# mainboard.net
KiCad netlist of a schematic drawn in EAGLE
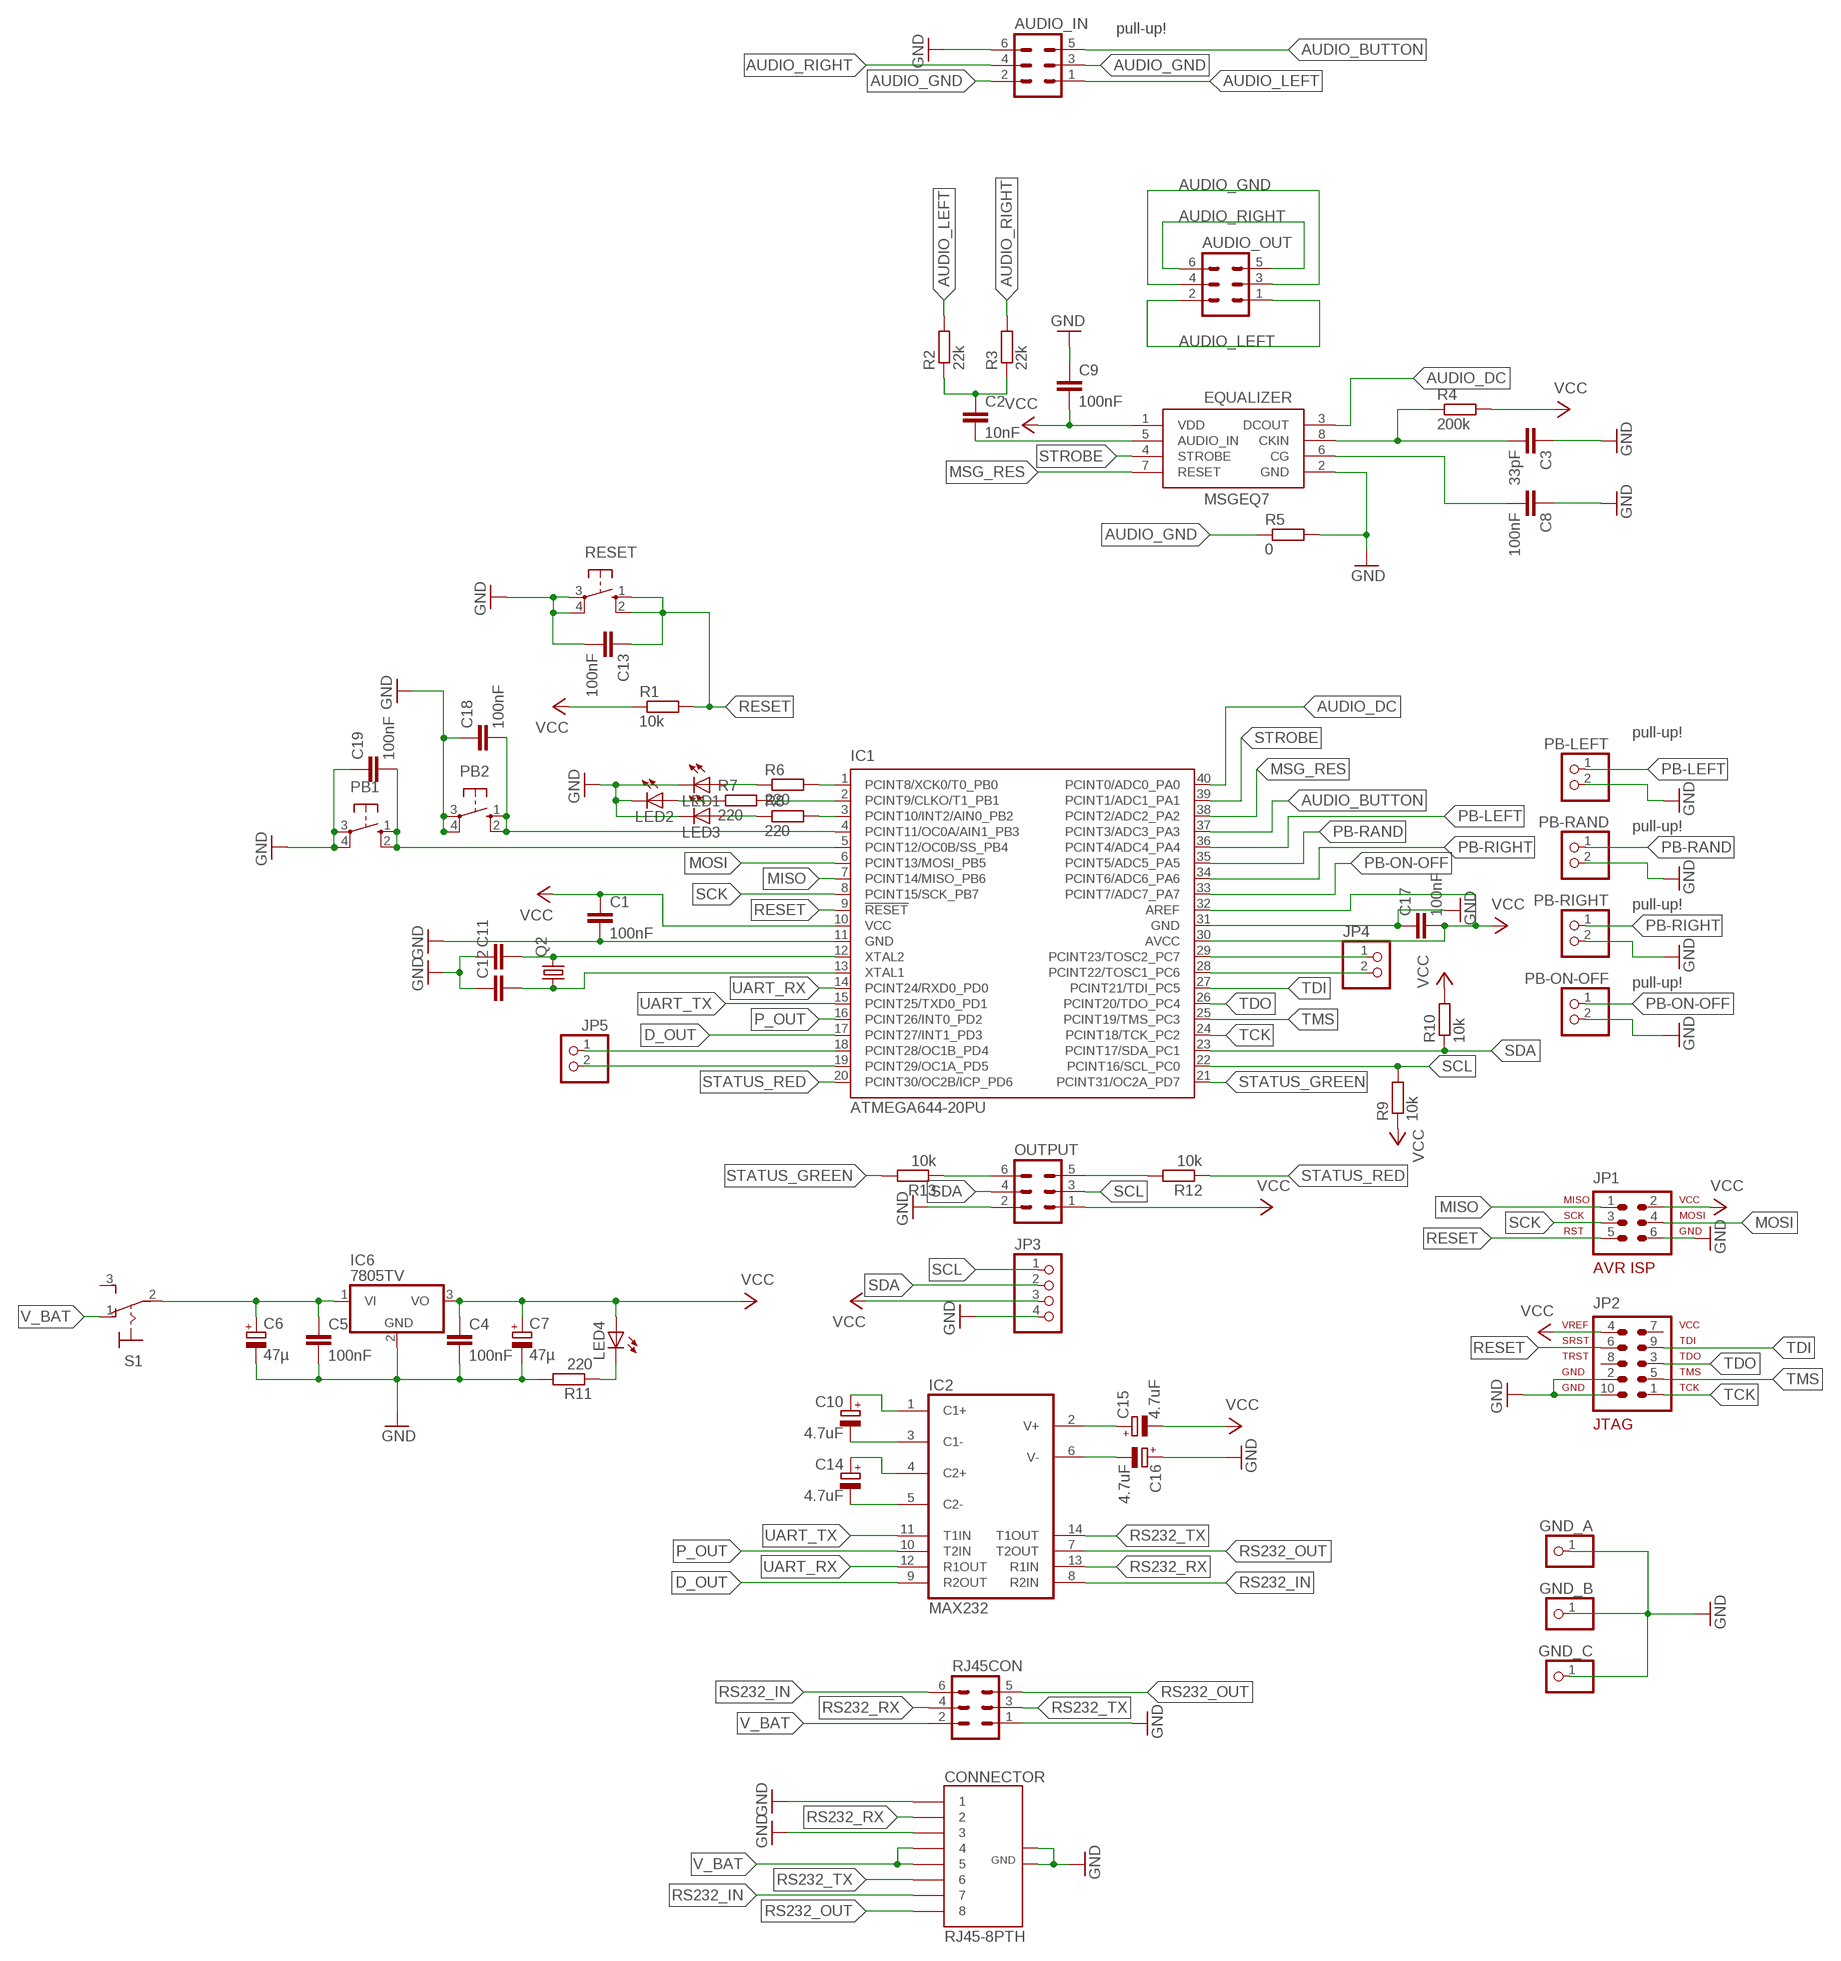
[diagram p0: schematic, sheet 1]

(export (version "E")
  (design (tool "Eeschema 10.0.6"))
  (components
    (comp (ref "AUDIO_IN")
      (value "ML6")
      (footprint "eagle-import:ML6")
      (fields (field (name "OC_FARNELL") "unknown") (field (name "OC_NEWARK") "unknown"))
      (libsource (lib "eagle-import") (part "ML6"))
    )
    (comp (ref "AUDIO_OUT")
      (value "ML6")
      (footprint "eagle-import:ML6")
      (libsource (lib "eagle-import") (part "ML6"))
    )
    (comp (ref "C1")
      (value "100nF")
      (footprint "eagle-import:C1206")
      (libsource (lib "eagle-import") (part "C-EUC1206"))
    )
    (comp (ref "C2")
      (value "10nF")
      (footprint "eagle-import:C1206")
      (libsource (lib "eagle-import") (part "C-EUC1206"))
    )
    (comp (ref "C3")
      (value "33pF")
      (footprint "eagle-import:C1206")
      (libsource (lib "eagle-import") (part "C-EUC1206"))
    )
    (comp (ref "C4")
      (value "100nF")
      (footprint "eagle-import:C1206")
      (libsource (lib "eagle-import") (part "C-EUC1206"))
    )
    (comp (ref "C5")
      (value "100nF")
      (footprint "eagle-import:C1206")
      (libsource (lib "eagle-import") (part "C-EUC1206"))
    )
    (comp (ref "C6")
      (value "47µ")
      (footprint "eagle-import:E2,5-6")
      (libsource (lib "eagle-import") (part "CPOL-EUE2.5-6"))
    )
    (comp (ref "C7")
      (value "47µ")
      (footprint "eagle-import:E2,5-6")
      (libsource (lib "eagle-import") (part "CPOL-EUE2.5-6"))
    )
    (comp (ref "C8")
      (value "100nF")
      (footprint "eagle-import:C1206")
      (libsource (lib "eagle-import") (part "C-EUC1206"))
    )
    (comp (ref "C9")
      (value "100nF")
      (footprint "eagle-import:C1206")
      (libsource (lib "eagle-import") (part "C-EUC1206"))
    )
    (comp (ref "C10")
      (value "4.7uF")
      (footprint "eagle-import:E2-5")
      (libsource (lib "eagle-import") (part "CPOL-EUE2-5"))
    )
    (comp (ref "C11")
      (value "C-EUC1206")
      (footprint "eagle-import:C1206")
      (libsource (lib "eagle-import") (part "C-EUC1206"))
    )
    (comp (ref "C12")
      (value "C-EUC1206")
      (footprint "eagle-import:C1206")
      (libsource (lib "eagle-import") (part "C-EUC1206"))
    )
    (comp (ref "C13")
      (value "100nF")
      (footprint "eagle-import:C1206")
      (libsource (lib "eagle-import") (part "C-EUC1206"))
    )
    (comp (ref "C14")
      (value "4.7uF")
      (footprint "eagle-import:E2-5")
      (libsource (lib "eagle-import") (part "CPOL-EUE2-5"))
    )
    (comp (ref "C15")
      (value "4.7uF")
      (footprint "eagle-import:E2-5")
      (libsource (lib "eagle-import") (part "CPOL-EUE2-5"))
    )
    (comp (ref "C16")
      (value "4.7uF")
      (footprint "eagle-import:E2-5")
      (libsource (lib "eagle-import") (part "CPOL-EUE2-5"))
    )
    (comp (ref "C17")
      (value "100nF")
      (footprint "eagle-import:C1206")
      (libsource (lib "eagle-import") (part "C-EUC1206"))
    )
    (comp (ref "C18")
      (value "100nF")
      (footprint "eagle-import:C1206")
      (libsource (lib "eagle-import") (part "C-EUC1206"))
    )
    (comp (ref "C19")
      (value "100nF")
      (footprint "eagle-import:C1206")
      (libsource (lib "eagle-import") (part "C-EUC1206"))
    )
    (comp (ref "CONNECTOR")
      (value "RJ45-8PTH")
      (footprint "eagle-import:RJ45-8")
      (libsource (lib "eagle-import") (part "RJ45-8PTH"))
    )
    (comp (ref "EQUALIZER")
      (value "MSGEQ7")
      (footprint "eagle-import:DIL-08")
      (libsource (lib "eagle-import") (part "MSGEQ7"))
    )
    (comp (ref "GND_A")
      (value "PINHD-1X1")
      (footprint "eagle-import:1X01")
      (libsource (lib "eagle-import") (part "PINHD-1X1"))
    )
    (comp (ref "GND_B")
      (value "PINHD-1X1")
      (footprint "eagle-import:1X01")
      (libsource (lib "eagle-import") (part "PINHD-1X1"))
    )
    (comp (ref "GND_C")
      (value "PINHD-1X1")
      (footprint "eagle-import:1X01")
      (libsource (lib "eagle-import") (part "PINHD-1X1"))
    )
    (comp (ref "IC1")
      (value "ATMEGA644-20PU")
      (footprint "eagle-import:DIL40")
      (libsource (lib "eagle-import") (part "ATMEGA644-PU20"))
    )
    (comp (ref "IC2")
      (value "MAX232")
      (footprint "eagle-import:DIL16")
      (fields (field (name "MF") "MAXIM") (field (name "MPN") "MAX232ACPE+"))
      (libsource (lib "eagle-import") (part "MAX232"))
    )
    (comp (ref "IC6")
      (value "7805TV")
      (footprint "eagle-import:TO220V")
      (libsource (lib "eagle-import") (part "78TV05"))
    )
    (comp (ref "JP1")
      (value "AVR-ISP-6VERT")
      (footprint "eagle-import:AVR-ISP-6")
      (libsource (lib "eagle-import") (part "AVR-ISP-6VERT"))
    )
    (comp (ref "JP2")
      (value "AVR-JTAG-10")
      (footprint "eagle-import:AVR-JTAG-10")
      (libsource (lib "eagle-import") (part "AVR-JTAG-10"))
    )
    (comp (ref "JP3")
      (value "PINHD-1X4")
      (footprint "eagle-import:1X04")
      (libsource (lib "eagle-import") (part "PINHD-1X4"))
    )
    (comp (ref "JP4")
      (value "PINHD-1X2")
      (footprint "eagle-import:1X02")
      (libsource (lib "eagle-import") (part "PINHD-1X2"))
    )
    (comp (ref "JP5")
      (value "PINHD-1X2")
      (footprint "eagle-import:1X02")
      (libsource (lib "eagle-import") (part "PINHD-1X2"))
    )
    (comp (ref "LED1")
      (value "LED5MM")
      (footprint "eagle-import:LED5MM")
      (libsource (lib "eagle-import") (part "LED5MM"))
    )
    (comp (ref "LED2")
      (value "LED5MM")
      (footprint "eagle-import:LED5MM")
      (libsource (lib "eagle-import") (part "LED5MM"))
    )
    (comp (ref "LED3")
      (value "LED5MM")
      (footprint "eagle-import:LED5MM")
      (libsource (lib "eagle-import") (part "LED5MM"))
    )
    (comp (ref "LED4")
      (value "LED5MM")
      (footprint "eagle-import:LED5MM")
      (libsource (lib "eagle-import") (part "LED5MM"))
    )
    (comp (ref "OUTPUT")
      (value "ML6")
      (footprint "eagle-import:ML6")
      (libsource (lib "eagle-import") (part "ML6"))
    )
    (comp (ref "PB-LEFT")
      (value "PINHD-1X2")
      (footprint "eagle-import:1X02")
      (libsource (lib "eagle-import") (part "PINHD-1X2"))
    )
    (comp (ref "PB-ON-OFF")
      (value "PINHD-1X2")
      (footprint "eagle-import:1X02")
      (libsource (lib "eagle-import") (part "PINHD-1X2"))
    )
    (comp (ref "PB-RAND")
      (value "PINHD-1X2")
      (footprint "eagle-import:1X02")
      (libsource (lib "eagle-import") (part "PINHD-1X2"))
    )
    (comp (ref "PB-RIGHT")
      (value "PINHD-1X2")
      (footprint "eagle-import:1X02")
      (libsource (lib "eagle-import") (part "PINHD-1X2"))
    )
    (comp (ref "PB1")
      (value "10-XX")
      (footprint "eagle-import:B3F-10XX")
      (fields
        (field (name "MPN") "B3F-1000")
        (field (name "MPN_1") "B3F-1000")
        (field (name "OC_FARNELL") "176432")
        (field (name "OC_NEWARK") "36M3542")
      )
      (libsource (lib "eagle-import") (part "10-XX"))
    )
    (comp (ref "PB2")
      (value "10-XX")
      (footprint "eagle-import:B3F-10XX")
      (fields
        (field (name "MPN") "B3F-1000")
        (field (name "MPN_1") "B3F-1000")
        (field (name "OC_FARNELL") "176432")
        (field (name "OC_NEWARK") "36M3542")
      )
      (libsource (lib "eagle-import") (part "10-XX"))
    )
    (comp (ref "Q2")
      (value "CRYSTALHC49S")
      (footprint "eagle-import:HC49_S")
      (libsource (lib "eagle-import") (part "CRYSTALHC49S"))
    )
    (comp (ref "R1")
      (value "10k")
      (footprint "eagle-import:0207_10")
      (libsource (lib "eagle-import") (part "R-EU_0207/10"))
    )
    (comp (ref "R2")
      (value "22k")
      (footprint "eagle-import:0207_10")
      (libsource (lib "eagle-import") (part "R-EU_0207/10"))
    )
    (comp (ref "R3")
      (value "22k")
      (footprint "eagle-import:0207_10")
      (libsource (lib "eagle-import") (part "R-EU_0207/10"))
    )
    (comp (ref "R4")
      (value "200k")
      (footprint "eagle-import:0207_10")
      (libsource (lib "eagle-import") (part "R-EU_0207/10"))
    )
    (comp (ref "R5")
      (value "0")
      (footprint "eagle-import:M1206")
      (libsource (lib "eagle-import") (part "R-EU_M1206"))
    )
    (comp (ref "R6")
      (value "220")
      (footprint "eagle-import:0207_10")
      (libsource (lib "eagle-import") (part "R-EU_0207/10"))
    )
    (comp (ref "R7")
      (value "220")
      (footprint "eagle-import:0207_10")
      (libsource (lib "eagle-import") (part "R-EU_0207/10"))
    )
    (comp (ref "R8")
      (value "220")
      (footprint "eagle-import:0207_10")
      (libsource (lib "eagle-import") (part "R-EU_0207/10"))
    )
    (comp (ref "R9")
      (value "10k")
      (footprint "eagle-import:0207_10")
      (libsource (lib "eagle-import") (part "R-EU_0207/10"))
    )
    (comp (ref "R10")
      (value "10k")
      (footprint "eagle-import:0207_12")
      (libsource (lib "eagle-import") (part "R-EU_0207/12"))
    )
    (comp (ref "R11")
      (value "220")
      (footprint "eagle-import:0207_10")
      (libsource (lib "eagle-import") (part "R-EU_0207/10"))
    )
    (comp (ref "R12")
      (value "10k")
      (footprint "eagle-import:0207_15")
      (libsource (lib "eagle-import") (part "R-EU_0207/15"))
    )
    (comp (ref "R13")
      (value "10k")
      (footprint "eagle-import:0207_12")
      (libsource (lib "eagle-import") (part "R-EU_0207/12"))
    )
    (comp (ref "RESET")
      (value "10-XX")
      (footprint "eagle-import:B3F-10XX")
      (fields (field (name "MPN") "B3F-1000"))
      (libsource (lib "eagle-import") (part "10-XX"))
    )
    (comp (ref "RJ45CON")
      (value "ML6")
      (footprint "eagle-import:ML6")
      (libsource (lib "eagle-import") (part "ML6"))
    )
    (comp (ref "S1")
      (value "M9040P")
      (footprint "eagle-import:M9040P")
      (libsource (lib "eagle-import") (part "M9040P"))
    )
  )
  (nets
    (net (code "1") (name "AUDIO_BUTTON") (class "Default")
      (node (ref "AUDIO_IN") (pin "5") (pinfunction "5_5") (pintype "passive"))
      (node (ref "IC1") (pin "37") (pinfunction "PCINT3/ADC3_PA3_37") (pintype "bidirectional"))
    )
    (net (code "2") (name "AUDIO_DC") (class "Default")
      (node (ref "EQUALIZER") (pin "3") (pinfunction "DCOUT_3") (pintype "bidirectional"))
      (node (ref "IC1") (pin "40") (pinfunction "PCINT0/ADC0_PA0_40") (pintype "bidirectional"))
    )
    (net (code "3") (name "AUDIO_GND") (class "Default")
      (node (ref "AUDIO_IN") (pin "2") (pinfunction "2_2") (pintype "passive"))
      (node (ref "AUDIO_IN") (pin "3") (pinfunction "3_3") (pintype "passive"))
      (node (ref "AUDIO_OUT") (pin "3") (pinfunction "3_3") (pintype "passive"))
      (node (ref "AUDIO_OUT") (pin "4") (pinfunction "4_4") (pintype "passive"))
      (node (ref "R5") (pin "1") (pinfunction "1_1") (pintype "passive"))
    )
    (net (code "4") (name "AUDIO_LEFT") (class "Default")
      (node (ref "AUDIO_IN") (pin "1") (pinfunction "1_1") (pintype "passive"))
      (node (ref "AUDIO_OUT") (pin "1") (pinfunction "1_1") (pintype "passive"))
      (node (ref "AUDIO_OUT") (pin "2") (pinfunction "2_2") (pintype "passive"))
      (node (ref "R2") (pin "2") (pinfunction "2_2") (pintype "passive"))
    )
    (net (code "5") (name "AUDIO_RIGHT") (class "Default")
      (node (ref "AUDIO_IN") (pin "4") (pinfunction "4_4") (pintype "passive"))
      (node (ref "AUDIO_OUT") (pin "5") (pinfunction "5_5") (pintype "passive"))
      (node (ref "AUDIO_OUT") (pin "6") (pinfunction "6_6") (pintype "passive"))
      (node (ref "R3") (pin "2") (pinfunction "2_2") (pintype "passive"))
    )
    (net (code "6") (name "D_OUT") (class "Default")
      (node (ref "IC1") (pin "17") (pinfunction "PCINT27/INT1_PD3_17") (pintype "bidirectional"))
      (node (ref "IC2") (pin "9") (pinfunction "R2OUT_9") (pintype "output"))
    )
    (net (code "7") (name "GND") (class "Default")
      (node (ref "AUDIO_IN") (pin "6") (pinfunction "6_6") (pintype "passive"))
      (node (ref "C1") (pin "2") (pinfunction "2_2") (pintype "passive"))
      (node (ref "C11") (pin "1") (pinfunction "1_1") (pintype "passive"))
      (node (ref "C12") (pin "1") (pinfunction "1_1") (pintype "passive"))
      (node (ref "C13") (pin "2") (pinfunction "2_2") (pintype "passive"))
      (node (ref "C16") (pin "+") (pinfunction "+_+") (pintype "passive"))
      (node (ref "C17") (pin "1") (pinfunction "1_1") (pintype "passive"))
      (node (ref "C18") (pin "1") (pinfunction "1_1") (pintype "passive"))
      (node (ref "C19") (pin "1") (pinfunction "1_1") (pintype "passive"))
      (node (ref "C3") (pin "1") (pinfunction "1_1") (pintype "passive"))
      (node (ref "C4") (pin "2") (pinfunction "2_2") (pintype "passive"))
      (node (ref "C5") (pin "2") (pinfunction "2_2") (pintype "passive"))
      (node (ref "C6") (pin "-") (pinfunction "-_-") (pintype "passive"))
      (node (ref "C7") (pin "-") (pinfunction "-_-") (pintype "passive"))
      (node (ref "C8") (pin "1") (pinfunction "1_1") (pintype "passive"))
      (node (ref "C9") (pin "1") (pinfunction "1_1") (pintype "passive"))
      (node (ref "CONNECTOR") (pin "1") (pinfunction "1_1") (pintype "bidirectional"))
      (node (ref "CONNECTOR") (pin "3") (pinfunction "3_3") (pintype "bidirectional"))
      (node (ref "CONNECTOR") (pin "GND_1") (pinfunction "GND_1_GND_1") (pintype "bidirectional"))
      (node (ref "CONNECTOR") (pin "GND_2") (pinfunction "GND_2_GND_2") (pintype "bidirectional"))
      (node (ref "EQUALIZER") (pin "2") (pinfunction "GND_2") (pintype "bidirectional"))
      (node (ref "GND_A") (pin "1") (pinfunction "1_1") (pintype "passive"))
      (node (ref "GND_B") (pin "1") (pinfunction "1_1") (pintype "passive"))
      (node (ref "GND_C") (pin "1") (pinfunction "1_1") (pintype "passive"))
      (node (ref "IC1") (pin "11") (pinfunction "GND_11") (pintype "power_in"))
      (node (ref "IC1") (pin "31") (pinfunction "GND_31") (pintype "power_in"))
      (node (ref "IC6") (pin "2") (pinfunction "GND_2") (pintype "passive"))
      (node (ref "JP1") (pin "6") (pinfunction "6_6") (pintype "passive"))
      (node (ref "JP2") (pin "10") (pinfunction "10_10") (pintype "passive"))
      (node (ref "JP2") (pin "2") (pinfunction "2_2") (pintype "passive"))
      (node (ref "JP3") (pin "4") (pinfunction "4_4") (pintype "passive"))
      (node (ref "LED1") (pin "K") (pinfunction "C_K") (pintype "passive"))
      (node (ref "LED2") (pin "K") (pinfunction "C_K") (pintype "passive"))
      (node (ref "LED3") (pin "K") (pinfunction "C_K") (pintype "passive"))
      (node (ref "OUTPUT") (pin "2") (pinfunction "2_2") (pintype "passive"))
      (node (ref "PB-LEFT") (pin "2") (pinfunction "2_2") (pintype "passive"))
      (node (ref "PB-ON-OFF") (pin "2") (pinfunction "2_2") (pintype "passive"))
      (node (ref "PB-RAND") (pin "2") (pinfunction "2_2") (pintype "passive"))
      (node (ref "PB-RIGHT") (pin "2") (pinfunction "2_2") (pintype "passive"))
      (node (ref "PB1") (pin "3") (pinfunction "P_3") (pintype "passive"))
      (node (ref "PB1") (pin "4") (pinfunction "P1_4") (pintype "passive"))
      (node (ref "PB2") (pin "3") (pinfunction "P_3") (pintype "passive"))
      (node (ref "PB2") (pin "4") (pinfunction "P1_4") (pintype "passive"))
      (node (ref "R11") (pin "2") (pinfunction "2_2") (pintype "passive"))
      (node (ref "R5") (pin "2") (pinfunction "2_2") (pintype "passive"))
      (node (ref "RESET") (pin "3") (pinfunction "P_3") (pintype "passive"))
      (node (ref "RESET") (pin "4") (pinfunction "P1_4") (pintype "passive"))
      (node (ref "RJ45CON") (pin "1") (pinfunction "1_1") (pintype "passive"))
    )
    (net (code "8") (name "MISO") (class "Default")
      (node (ref "IC1") (pin "7") (pinfunction "PCINT14/MISO_PB6_7") (pintype "bidirectional"))
      (node (ref "JP1") (pin "1") (pinfunction "1_1") (pintype "passive"))
    )
    (net (code "9") (name "MOSI") (class "Default")
      (node (ref "IC1") (pin "6") (pinfunction "PCINT13/MOSI_PB5_6") (pintype "bidirectional"))
      (node (ref "JP1") (pin "4") (pinfunction "4_4") (pintype "passive"))
    )
    (net (code "10") (name "MSG_RES") (class "Default")
      (node (ref "EQUALIZER") (pin "7") (pinfunction "RESET_7") (pintype "input"))
      (node (ref "IC1") (pin "38") (pinfunction "PCINT2/ADC2_PA2_38") (pintype "bidirectional"))
    )
    (net (code "11") (name "Net-(C2-Pad1)") (class "Default")
      (node (ref "C2") (pin "1") (pinfunction "1_1") (pintype "passive"))
      (node (ref "R2") (pin "1") (pinfunction "1_1") (pintype "passive"))
      (node (ref "R3") (pin "1") (pinfunction "1_1") (pintype "passive"))
    )
    (net (code "12") (name "Net-(EQUALIZER-AUDIO_IN)") (class "Default")
      (node (ref "C2") (pin "2") (pinfunction "2_2") (pintype "passive"))
      (node (ref "EQUALIZER") (pin "5") (pinfunction "AUDIO_IN_5") (pintype "input"))
    )
    (net (code "13") (name "Net-(EQUALIZER-CG)") (class "Default")
      (node (ref "C8") (pin "2") (pinfunction "2_2") (pintype "passive"))
      (node (ref "EQUALIZER") (pin "6") (pinfunction "CG_6") (pintype "bidirectional"))
    )
    (net (code "14") (name "Net-(EQUALIZER-CKIN)") (class "Default")
      (node (ref "C3") (pin "2") (pinfunction "2_2") (pintype "passive"))
      (node (ref "EQUALIZER") (pin "8") (pinfunction "CKIN_8") (pintype "bidirectional"))
      (node (ref "R4") (pin "1") (pinfunction "1_1") (pintype "passive"))
    )
    (net (code "15") (name "Net-(IC1-PCINT8{slash}XCK0{slash}T0_PB0)") (class "Default")
      (node (ref "IC1") (pin "1") (pinfunction "PCINT8/XCK0/T0_PB0_1") (pintype "bidirectional"))
      (node (ref "R6") (pin "2") (pinfunction "2_2") (pintype "passive"))
    )
    (net (code "16") (name "Net-(IC1-PCINT9{slash}CLKO{slash}T1_PB1)") (class "Default")
      (node (ref "IC1") (pin "2") (pinfunction "PCINT9/CLKO/T1_PB1_2") (pintype "bidirectional"))
      (node (ref "R7") (pin "2") (pinfunction "2_2") (pintype "passive"))
    )
    (net (code "17") (name "Net-(IC1-PCINT10{slash}INT2{slash}AIN0_PB2)") (class "Default")
      (node (ref "IC1") (pin "3") (pinfunction "PCINT10/INT2/AIN0_PB2_3") (pintype "bidirectional"))
      (node (ref "R8") (pin "2") (pinfunction "2_2") (pintype "passive"))
    )
    (net (code "18") (name "Net-(IC1-PCINT11{slash}OC0A{slash}AIN1_PB3)") (class "Default")
      (node (ref "C18") (pin "2") (pinfunction "2_2") (pintype "passive"))
      (node (ref "IC1") (pin "4") (pinfunction "PCINT11/OC0A/AIN1_PB3_4") (pintype "bidirectional"))
      (node (ref "PB2") (pin "1") (pinfunction "S_1") (pintype "passive"))
      (node (ref "PB2") (pin "2") (pinfunction "S1_2") (pintype "passive"))
    )
    (net (code "19") (name "Net-(IC1-PCINT12{slash}OC0B{slash}SS_PB4)") (class "Default")
      (node (ref "C19") (pin "2") (pinfunction "2_2") (pintype "passive"))
      (node (ref "IC1") (pin "5") (pinfunction "PCINT12/OC0B/SS_PB4_5") (pintype "bidirectional"))
      (node (ref "PB1") (pin "1") (pinfunction "S_1") (pintype "passive"))
      (node (ref "PB1") (pin "2") (pinfunction "S1_2") (pintype "passive"))
    )
    (net (code "20") (name "Net-(IC1-PCINT22{slash}TOSC1_PC6)") (class "Default")
      (node (ref "IC1") (pin "28") (pinfunction "PCINT22/TOSC1_PC6_28") (pintype "bidirectional"))
      (node (ref "JP4") (pin "2") (pinfunction "2_2") (pintype "passive"))
    )
    (net (code "21") (name "Net-(IC1-PCINT23{slash}TOSC2_PC7)") (class "Default")
      (node (ref "IC1") (pin "29") (pinfunction "PCINT23/TOSC2_PC7_29") (pintype "bidirectional"))
      (node (ref "JP4") (pin "1") (pinfunction "1_1") (pintype "passive"))
    )
    (net (code "22") (name "Net-(IC1-PCINT28{slash}OC1B_PD4)") (class "Default")
      (node (ref "IC1") (pin "18") (pinfunction "PCINT28/OC1B_PD4_18") (pintype "bidirectional"))
      (node (ref "JP5") (pin "1") (pinfunction "1_1") (pintype "passive"))
    )
    (net (code "23") (name "Net-(IC1-PCINT29{slash}OC1A_PD5)") (class "Default")
      (node (ref "IC1") (pin "19") (pinfunction "PCINT29/OC1A_PD5_19") (pintype "bidirectional"))
      (node (ref "JP5") (pin "2") (pinfunction "2_2") (pintype "passive"))
    )
    (net (code "24") (name "Net-(IC1-XTAL1)") (class "Default")
      (node (ref "C12") (pin "2") (pinfunction "2_2") (pintype "passive"))
      (node (ref "IC1") (pin "13") (pinfunction "XTAL1_13") (pintype "input"))
      (node (ref "Q2") (pin "1") (pinfunction "1_1") (pintype "passive"))
    )
    (net (code "25") (name "Net-(IC1-XTAL2)") (class "Default")
      (node (ref "C11") (pin "2") (pinfunction "2_2") (pintype "passive"))
      (node (ref "IC1") (pin "12") (pinfunction "XTAL2_12") (pintype "output"))
      (node (ref "Q2") (pin "2") (pinfunction "2_2") (pintype "passive"))
    )
    (net (code "26") (name "Net-(IC2A-C1+)") (class "Default")
      (node (ref "C10") (pin "+") (pinfunction "+_+") (pintype "passive"))
      (node (ref "IC2") (pin "1") (pinfunction "C1+_1") (pintype "bidirectional"))
    )
    (net (code "27") (name "Net-(IC2A-C1-)") (class "Default")
      (node (ref "C10") (pin "-") (pinfunction "-_-") (pintype "passive"))
      (node (ref "IC2") (pin "3") (pinfunction "C1-_3") (pintype "bidirectional"))
    )
    (net (code "28") (name "Net-(IC2A-C2+)") (class "Default")
      (node (ref "C14") (pin "+") (pinfunction "+_+") (pintype "passive"))
      (node (ref "IC2") (pin "4") (pinfunction "C2+_4") (pintype "bidirectional"))
    )
    (net (code "29") (name "Net-(IC2A-C2-)") (class "Default")
      (node (ref "C14") (pin "-") (pinfunction "-_-") (pintype "passive"))
      (node (ref "IC2") (pin "5") (pinfunction "C2-_5") (pintype "bidirectional"))
    )
    (net (code "30") (name "Net-(IC2A-V+)") (class "Default")
      (node (ref "C15") (pin "+") (pinfunction "+_+") (pintype "passive"))
      (node (ref "IC2") (pin "2") (pinfunction "V+_2") (pintype "bidirectional"))
    )
    (net (code "31") (name "Net-(IC2A-V-)") (class "Default")
      (node (ref "C16") (pin "-") (pinfunction "-_-") (pintype "passive"))
      (node (ref "IC2") (pin "6") (pinfunction "V-_6") (pintype "bidirectional"))
    )
    (net (code "32") (name "Net-(IC6-VI)") (class "Default")
      (node (ref "C5") (pin "1") (pinfunction "1_1") (pintype "passive"))
      (node (ref "C6") (pin "+") (pinfunction "+_+") (pintype "passive"))
      (node (ref "IC6") (pin "1") (pinfunction "VI_1") (pintype "input"))
      (node (ref "S1") (pin "2") (pinfunction "P_2") (pintype "passive"))
    )
    (net (code "33") (name "Net-(LED1-PadA)") (class "Default")
      (node (ref "LED1") (pin "A") (pinfunction "A_A") (pintype "passive"))
      (node (ref "R6") (pin "1") (pinfunction "1_1") (pintype "passive"))
    )
    (net (code "34") (name "Net-(LED2-PadA)") (class "Default")
      (node (ref "LED2") (pin "A") (pinfunction "A_A") (pintype "passive"))
      (node (ref "R7") (pin "1") (pinfunction "1_1") (pintype "passive"))
    )
    (net (code "35") (name "Net-(LED3-PadA)") (class "Default")
      (node (ref "LED3") (pin "A") (pinfunction "A_A") (pintype "passive"))
      (node (ref "R8") (pin "1") (pinfunction "1_1") (pintype "passive"))
    )
    (net (code "36") (name "Net-(LED4-C)") (class "Default")
      (node (ref "LED4") (pin "K") (pinfunction "C_K") (pintype "passive"))
      (node (ref "R11") (pin "1") (pinfunction "1_1") (pintype "passive"))
    )
    (net (code "37") (name "Net-(OUTPUT-Pad5)") (class "Default")
      (node (ref "OUTPUT") (pin "5") (pinfunction "5_5") (pintype "passive"))
      (node (ref "R12") (pin "2") (pinfunction "2_2") (pintype "passive"))
    )
    (net (code "38") (name "Net-(OUTPUT-Pad6)") (class "Default")
      (node (ref "OUTPUT") (pin "6") (pinfunction "6_6") (pintype "passive"))
      (node (ref "R13") (pin "1") (pinfunction "1_1") (pintype "passive"))
    )
    (net (code "39") (name "PB-LEFT") (class "Default")
      (node (ref "IC1") (pin "36") (pinfunction "PCINT4/ADC4_PA4_36") (pintype "bidirectional"))
      (node (ref "PB-LEFT") (pin "1") (pinfunction "1_1") (pintype "passive"))
    )
    (net (code "40") (name "PB-ON-OFF") (class "Default")
      (node (ref "IC1") (pin "33") (pinfunction "PCINT7/ADC7_PA7_33") (pintype "bidirectional"))
      (node (ref "PB-ON-OFF") (pin "1") (pinfunction "1_1") (pintype "passive"))
    )
    (net (code "41") (name "PB-RAND") (class "Default")
      (node (ref "IC1") (pin "35") (pinfunction "PCINT5/ADC5_PA5_35") (pintype "bidirectional"))
      (node (ref "PB-RAND") (pin "1") (pinfunction "1_1") (pintype "passive"))
    )
    (net (code "42") (name "PB-RIGHT") (class "Default")
      (node (ref "IC1") (pin "34") (pinfunction "PCINT6/ADC6_PA6_34") (pintype "bidirectional"))
      (node (ref "PB-RIGHT") (pin "1") (pinfunction "1_1") (pintype "passive"))
    )
    (net (code "43") (name "P_OUT") (class "Default")
      (node (ref "IC1") (pin "16") (pinfunction "PCINT26/INT0_PD2_16") (pintype "bidirectional"))
      (node (ref "IC2") (pin "10") (pinfunction "T2IN_10") (pintype "input"))
    )
    (net (code "44") (name "RESET") (class "Default")
      (node (ref "C13") (pin "1") (pinfunction "1_1") (pintype "passive"))
      (node (ref "IC1") (pin "9") (pinfunction "~{RESET}_9") (pintype "input"))
      (node (ref "JP1") (pin "5") (pinfunction "5_5") (pintype "passive"))
      (node (ref "JP2") (pin "6") (pinfunction "6_6") (pintype "passive"))
      (node (ref "R1") (pin "2") (pinfunction "2_2") (pintype "passive"))
      (node (ref "RESET") (pin "1") (pinfunction "S_1") (pintype "passive"))
      (node (ref "RESET") (pin "2") (pinfunction "S1_2") (pintype "passive"))
    )
    (net (code "45") (name "RS232_IN") (class "Default")
      (node (ref "CONNECTOR") (pin "7") (pinfunction "7_7") (pintype "bidirectional"))
      (node (ref "IC2") (pin "8") (pinfunction "R2IN_8") (pintype "input"))
      (node (ref "RJ45CON") (pin "6") (pinfunction "6_6") (pintype "passive"))
    )
    (net (code "46") (name "RS232_OUT") (class "Default")
      (node (ref "CONNECTOR") (pin "8") (pinfunction "8_8") (pintype "bidirectional"))
      (node (ref "IC2") (pin "7") (pinfunction "T2OUT_7") (pintype "output"))
      (node (ref "RJ45CON") (pin "5") (pinfunction "5_5") (pintype "passive"))
    )
    (net (code "47") (name "RS232_RX") (class "Default")
      (node (ref "CONNECTOR") (pin "2") (pinfunction "2_2") (pintype "bidirectional"))
      (node (ref "IC2") (pin "13") (pinfunction "R1IN_13") (pintype "input"))
      (node (ref "RJ45CON") (pin "4") (pinfunction "4_4") (pintype "passive"))
    )
    (net (code "48") (name "RS232_TX") (class "Default")
      (node (ref "CONNECTOR") (pin "6") (pinfunction "6_6") (pintype "bidirectional"))
      (node (ref "IC2") (pin "14") (pinfunction "T1OUT_14") (pintype "output"))
      (node (ref "RJ45CON") (pin "3") (pinfunction "3_3") (pintype "passive"))
    )
    (net (code "49") (name "SCK") (class "Default")
      (node (ref "IC1") (pin "8") (pinfunction "PCINT15/SCK_PB7_8") (pintype "bidirectional"))
      (node (ref "JP1") (pin "3") (pinfunction "3_3") (pintype "passive"))
    )
    (net (code "50") (name "SCL") (class "Default")
      (node (ref "IC1") (pin "22") (pinfunction "PCINT16/SCL_PC0_22") (pintype "bidirectional"))
      (node (ref "JP3") (pin "1") (pinfunction "1_1") (pintype "passive"))
      (node (ref "OUTPUT") (pin "3") (pinfunction "3_3") (pintype "passive"))
      (node (ref "R9") (pin "2") (pinfunction "2_2") (pintype "passive"))
    )
    (net (code "51") (name "SDA") (class "Default")
      (node (ref "IC1") (pin "23") (pinfunction "PCINT17/SDA_PC1_23") (pintype "bidirectional"))
      (node (ref "JP3") (pin "2") (pinfunction "2_2") (pintype "passive"))
      (node (ref "OUTPUT") (pin "4") (pinfunction "4_4") (pintype "passive"))
      (node (ref "R10") (pin "1") (pinfunction "1_1") (pintype "passive"))
    )
    (net (code "52") (name "STATUS_GREEN") (class "Default")
      (node (ref "IC1") (pin "21") (pinfunction "PCINT31/OC2A_PD7_21") (pintype "bidirectional"))
      (node (ref "R13") (pin "2") (pinfunction "2_2") (pintype "passive"))
    )
    (net (code "53") (name "STATUS_RED") (class "Default")
      (node (ref "IC1") (pin "20") (pinfunction "PCINT30/OC2B/ICP_PD6_20") (pintype "bidirectional"))
      (node (ref "R12") (pin "1") (pinfunction "1_1") (pintype "passive"))
    )
    (net (code "54") (name "STROBE") (class "Default")
      (node (ref "EQUALIZER") (pin "4") (pinfunction "STROBE_4") (pintype "input"))
      (node (ref "IC1") (pin "39") (pinfunction "PCINT1/ADC1_PA1_39") (pintype "bidirectional"))
    )
    (net (code "55") (name "TCK") (class "Default")
      (node (ref "IC1") (pin "24") (pinfunction "PCINT18/TCK_PC2_24") (pintype "bidirectional"))
      (node (ref "JP2") (pin "1") (pinfunction "1_1") (pintype "passive"))
    )
    (net (code "56") (name "TDI") (class "Default")
      (node (ref "IC1") (pin "27") (pinfunction "PCINT21/TDI_PC5_27") (pintype "bidirectional"))
      (node (ref "JP2") (pin "9") (pinfunction "9_9") (pintype "passive"))
    )
    (net (code "57") (name "TDO") (class "Default")
      (node (ref "IC1") (pin "26") (pinfunction "PCINT20/TDO_PC4_26") (pintype "bidirectional"))
      (node (ref "JP2") (pin "3") (pinfunction "3_3") (pintype "passive"))
    )
    (net (code "58") (name "TMS") (class "Default")
      (node (ref "IC1") (pin "25") (pinfunction "PCINT19/TMS_PC3_25") (pintype "bidirectional"))
      (node (ref "JP2") (pin "5") (pinfunction "5_5") (pintype "passive"))
    )
    (net (code "59") (name "UART_RX") (class "Default")
      (node (ref "IC1") (pin "14") (pinfunction "PCINT24/RXD0_PD0_14") (pintype "bidirectional"))
      (node (ref "IC2") (pin "12") (pinfunction "R1OUT_12") (pintype "output"))
    )
    (net (code "60") (name "UART_TX") (class "Default")
      (node (ref "IC1") (pin "15") (pinfunction "PCINT25/TXD0_PD1_15") (pintype "bidirectional"))
      (node (ref "IC2") (pin "11") (pinfunction "T1IN_11") (pintype "input"))
    )
    (net (code "61") (name "VCC") (class "Default")
      (node (ref "C1") (pin "1") (pinfunction "1_1") (pintype "passive"))
      (node (ref "C15") (pin "-") (pinfunction "-_-") (pintype "passive"))
      (node (ref "C17") (pin "2") (pinfunction "2_2") (pintype "passive"))
      (node (ref "C4") (pin "1") (pinfunction "1_1") (pintype "passive"))
      (node (ref "C7") (pin "+") (pinfunction "+_+") (pintype "passive"))
      (node (ref "C9") (pin "2") (pinfunction "2_2") (pintype "passive"))
      (node (ref "EQUALIZER") (pin "1") (pinfunction "VDD_1") (pintype "input"))
      (node (ref "IC1") (pin "10") (pinfunction "VCC_10") (pintype "power_in"))
      (node (ref "IC1") (pin "30") (pinfunction "AVCC_30") (pintype "power_in"))
      (node (ref "IC1") (pin "32") (pinfunction "AREF_32") (pintype "passive"))
      (node (ref "IC6") (pin "3") (pinfunction "VO_3") (pintype "passive"))
      (node (ref "JP1") (pin "2") (pinfunction "2_2") (pintype "passive"))
      (node (ref "JP2") (pin "4") (pinfunction "4_4") (pintype "passive"))
      (node (ref "JP3") (pin "3") (pinfunction "3_3") (pintype "passive"))
      (node (ref "LED4") (pin "A") (pinfunction "A_A") (pintype "passive"))
      (node (ref "OUTPUT") (pin "1") (pinfunction "1_1") (pintype "passive"))
      (node (ref "R1") (pin "1") (pinfunction "1_1") (pintype "passive"))
      (node (ref "R10") (pin "2") (pinfunction "2_2") (pintype "passive"))
      (node (ref "R4") (pin "2") (pinfunction "2_2") (pintype "passive"))
      (node (ref "R9") (pin "1") (pinfunction "1_1") (pintype "passive"))
    )
    (net (code "62") (name "V_BAT") (class "Default")
      (node (ref "CONNECTOR") (pin "4") (pinfunction "4_4") (pintype "bidirectional"))
      (node (ref "CONNECTOR") (pin "5") (pinfunction "5_5") (pintype "bidirectional"))
      (node (ref "RJ45CON") (pin "2") (pinfunction "2_2") (pintype "passive"))
      (node (ref "S1") (pin "1") (pinfunction "O_1") (pintype "passive"))
    )
    (net (code "63") (name "unconnected-(JP2-Pad7)") (class "Default")
      (node (ref "JP2") (pin "7") (pinfunction "7_7") (pintype "passive"))
    )
    (net (code "64") (name "unconnected-(JP2-Pad8)") (class "Default")
      (node (ref "JP2") (pin "8") (pinfunction "8_8") (pintype "passive"))
    )
    (net (code "65") (name "unconnected-(S1-S-Pad3)") (class "Default")
      (node (ref "S1") (pin "3") (pinfunction "S_3") (pintype "passive"))
    )
  )
)
